# STM32.net
KiCad netlist of a schematic drawn in Altium Designer
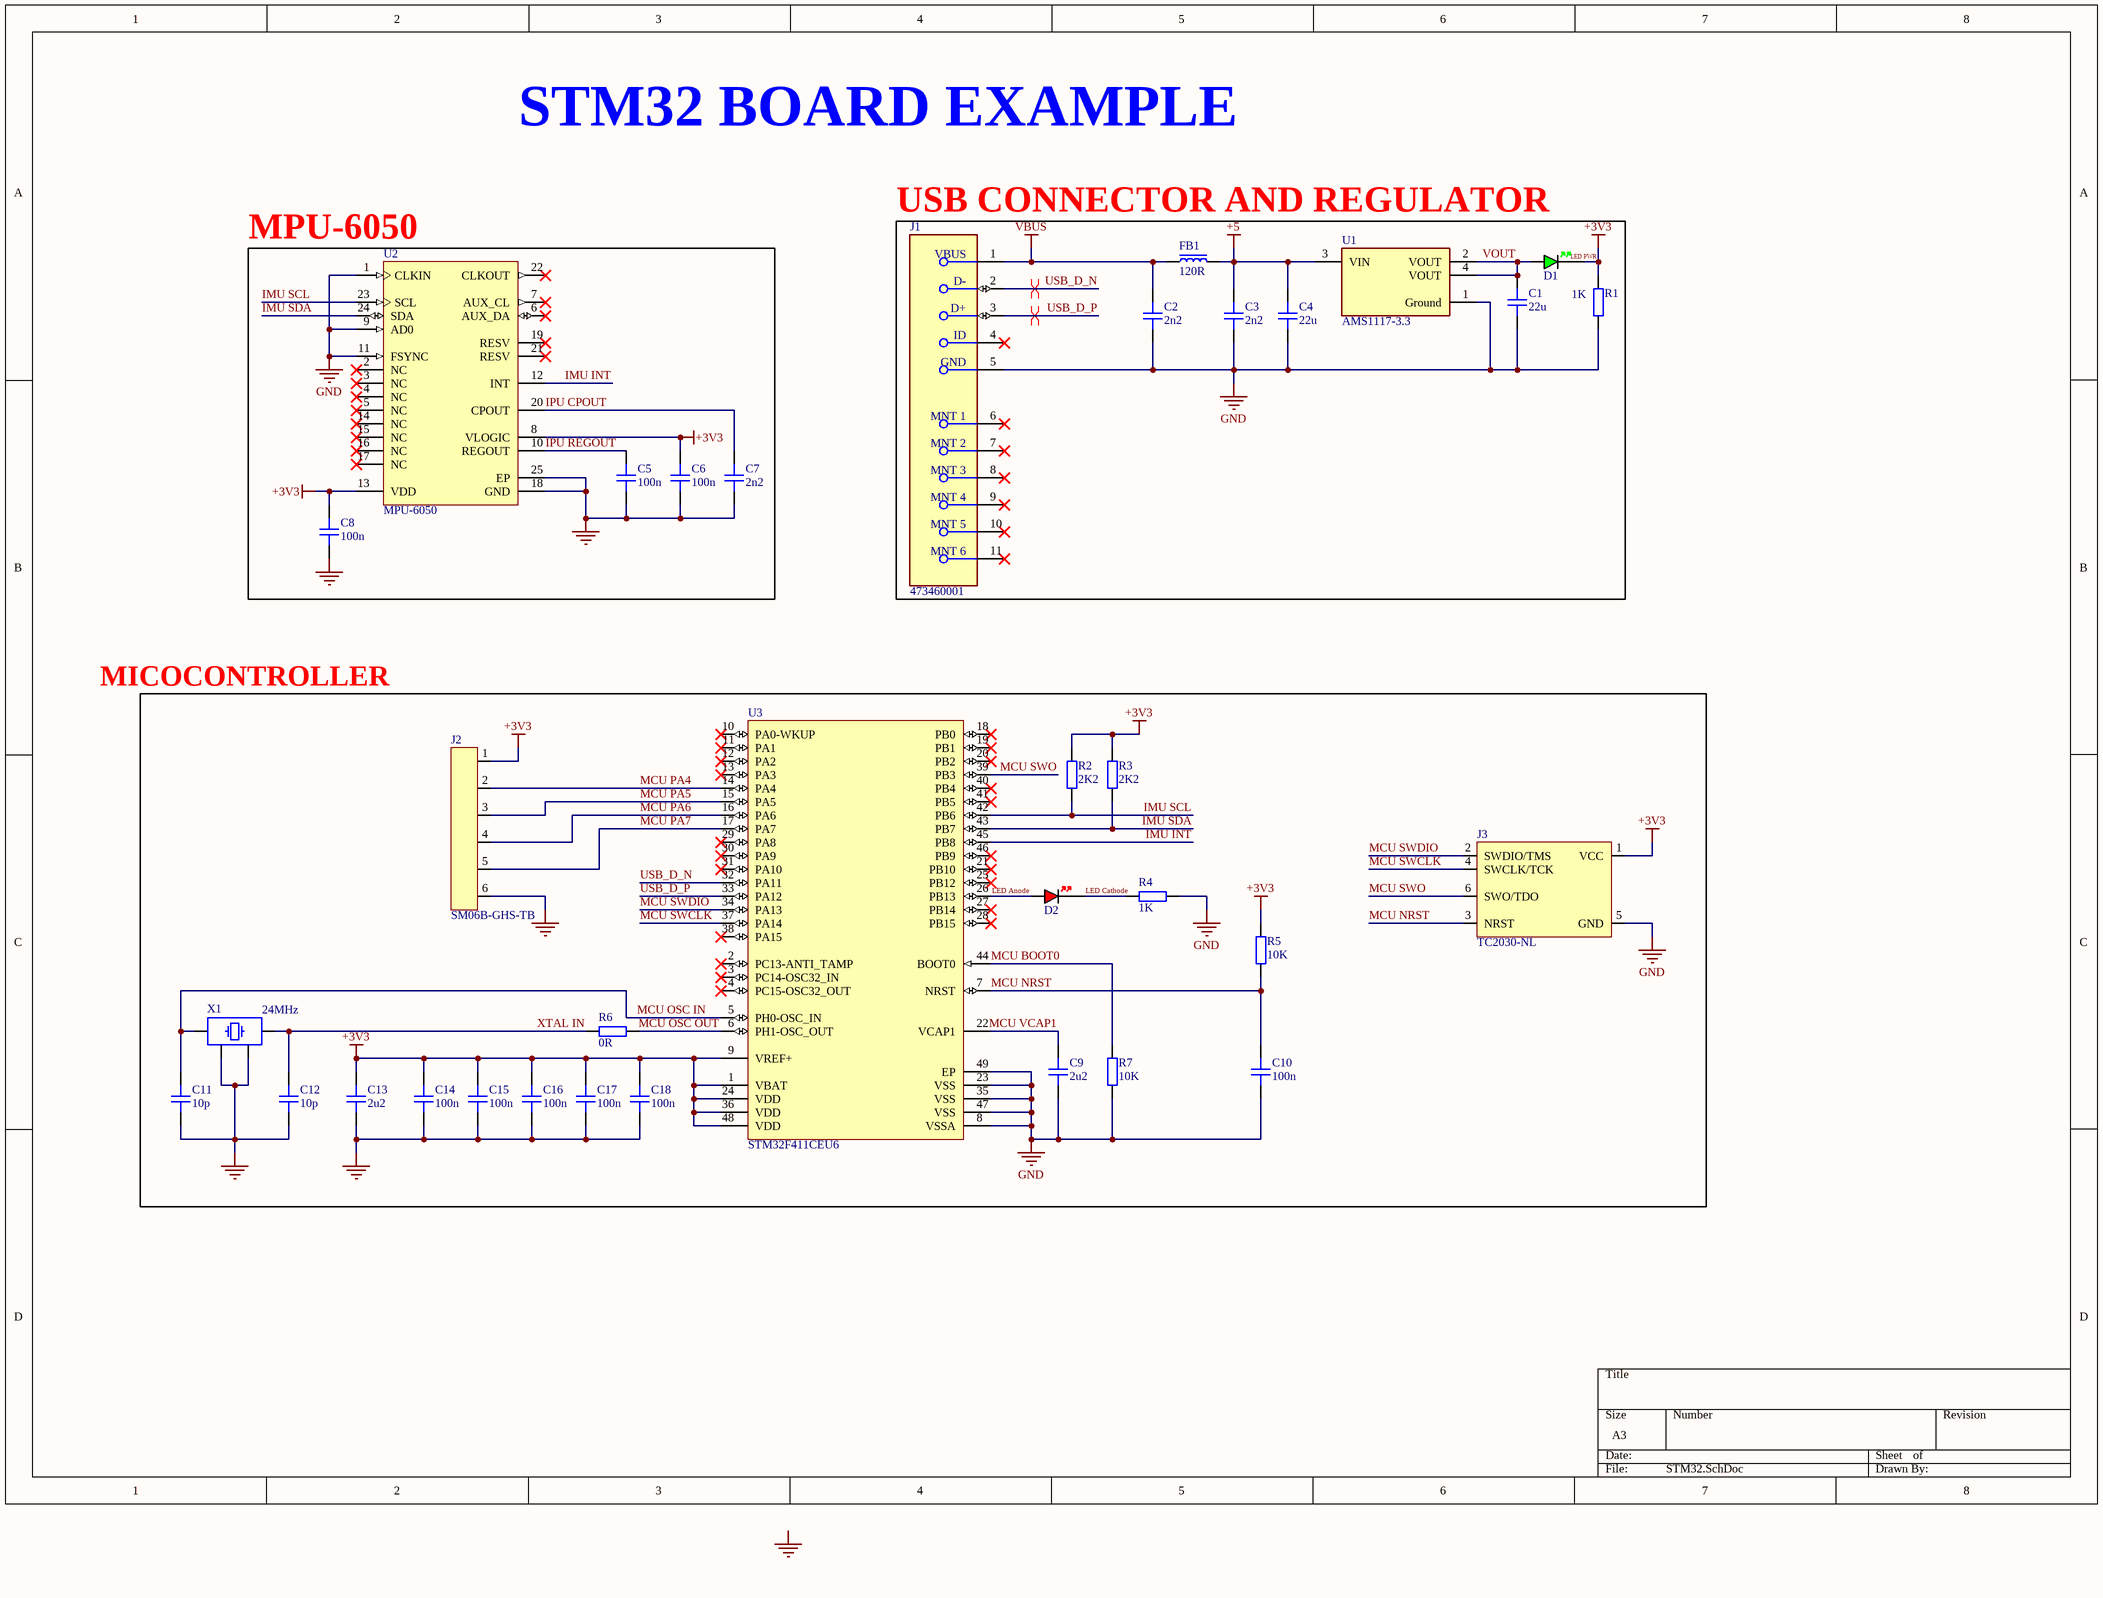
[diagram p0: STM32.SchDoc]

(export (version "E")
  (design (tool "Eeschema 10.0.6"))
  (components
    (comp (ref "C1")
      (value "22u")
      (footprint "CAP_0805")
      (description "Capacitor SMD 0805 16V")
      (libsource (lib "Schematic-Lib-PhilsLab") (part "CAP_0805_16V"))
    )
    (comp (ref "C2")
      (value "2n2")
      (footprint "CAP_0402")
      (description "Capacitor SMD 0402 16V")
      (libsource (lib "Schematic-Lib-PhilsLab") (part "CAP_0402_16V"))
    )
    (comp (ref "C3")
      (value "2n2")
      (footprint "CAP_0402")
      (description "Capacitor SMD 0402 16V")
      (libsource (lib "Schematic-Lib-PhilsLab") (part "CAP_0402_16V"))
    )
    (comp (ref "C4")
      (value "22u")
      (footprint "CAP_0805")
      (description "Capacitor SMD 0805 16V")
      (libsource (lib "Schematic-Lib-PhilsLab") (part "CAP_0805_16V"))
    )
    (comp (ref "C5")
      (value "100n")
      (footprint "CAP_0402")
      (description "Capacitor SMD 0402 16V")
      (libsource (lib "Schematic-Lib-PhilsLab") (part "CAP_0402_16V"))
    )
    (comp (ref "C6")
      (value "100n")
      (footprint "CAP_0402")
      (description "Capacitor SMD 0402 16V")
      (libsource (lib "Schematic-Lib-PhilsLab") (part "CAP_0402_16V"))
    )
    (comp (ref "C7")
      (value "2n2")
      (footprint "CAP_0402")
      (description "Capacitor SMD 0402 16V")
      (libsource (lib "Schematic-Lib-PhilsLab") (part "CAP_0402_16V"))
    )
    (comp (ref "C8")
      (value "100n")
      (footprint "CAP_0402")
      (description "Capacitor SMD 0402 16V")
      (libsource (lib "Schematic-Lib-PhilsLab") (part "CAP_0402_16V"))
    )
    (comp (ref "C9")
      (value "2u2")
      (footprint "CAP_0603")
      (description "Capacitor SMD 0603 16V")
      (libsource (lib "Schematic-Lib-PhilsLab") (part "CAP_0603_16V"))
    )
    (comp (ref "C10")
      (value "100n")
      (footprint "CAP_0402")
      (description "Capacitor SMD 0402 16V")
      (libsource (lib "Schematic-Lib-PhilsLab") (part "CAP_0402_16V"))
    )
    (comp (ref "C11")
      (value "10p")
      (footprint "CAP_0402")
      (description "Capacitor SMD 0402 16V")
      (libsource (lib "Schematic-Lib-PhilsLab") (part "CAP_0402_16V"))
    )
    (comp (ref "C12")
      (value "10p")
      (footprint "CAP_0402")
      (description "Capacitor SMD 0402 16V")
      (libsource (lib "Schematic-Lib-PhilsLab") (part "CAP_0402_16V"))
    )
    (comp (ref "C13")
      (value "2u2")
      (footprint "CAP_0603")
      (description "Capacitor SMD 0603 16V")
      (libsource (lib "Schematic-Lib-PhilsLab") (part "CAP_0603_16V"))
    )
    (comp (ref "C14")
      (value "100n")
      (footprint "CAP_0402")
      (description "Capacitor SMD 0402 16V")
      (libsource (lib "Schematic-Lib-PhilsLab") (part "CAP_0402_16V"))
    )
    (comp (ref "C15")
      (value "100n")
      (footprint "CAP_0402")
      (description "Capacitor SMD 0402 16V")
      (libsource (lib "Schematic-Lib-PhilsLab") (part "CAP_0402_16V"))
    )
    (comp (ref "C16")
      (value "100n")
      (footprint "CAP_0402")
      (description "Capacitor SMD 0402 16V")
      (libsource (lib "Schematic-Lib-PhilsLab") (part "CAP_0402_16V"))
    )
    (comp (ref "C17")
      (value "100n")
      (footprint "CAP_0402")
      (description "Capacitor SMD 0402 16V")
      (libsource (lib "Schematic-Lib-PhilsLab") (part "CAP_0402_16V"))
    )
    (comp (ref "C18")
      (value "100n")
      (footprint "CAP_0402")
      (description "Capacitor SMD 0402 16V")
      (libsource (lib "Schematic-Lib-PhilsLab") (part "CAP_0402_16V"))
    )
    (comp (ref "D1")
      (value "GREEN")
      (footprint "LED_0402_GREEN")
      (description "LED 0402 GREEN SMD")
      (libsource (lib "Schematic-Lib-PhilsLab") (part "LED_0402_GREEN"))
    )
    (comp (ref "D2")
      (value "RED")
      (footprint "LED_0402_RED")
      (description "LED 0402 RED SMD")
      (libsource (lib "Schematic-Lib-PhilsLab") (part "LED_0402_RED"))
    )
    (comp (ref "FB1")
      (value "120R")
      (footprint "FB_0603")
      (description "Ferrite Bead SMD 0603")
      (libsource (lib "Schematic-Lib-PhilsLab") (part "FB_0603"))
    )
    (comp (ref "J1")
      (value "473460001")
      (footprint "FP-473460001-MFG")
      (description "CONN RCPT USB2.0 MICRO B SMD R/A")
      (fields
        (field (name "OCTOPART") "https://octopart.com/47346-0001-molex-7164928")
        (field (name "MANUFACTURER") "Molex")
      )
      (libsource (lib "STMSch_Lib") (part "CMP-2000-05246-2"))
    )
    (comp (ref "J2")
      (value "SM06B-GHS-TB")
      (footprint "SM06B-GHS-TB")
      (description "Header Connector 6 Position 1.25MM Pitch SMD Horizontal JST GH")
      (fields (field (name "MANUFACTURER") "JST"))
      (libsource (lib "Schematic-Lib-PhilsLab") (part "SM06B-GHS-TB"))
    )
    (comp (ref "J3")
      (value "TC2030-NL")
      (footprint "TC2030-NL-FP")
      (description "Tag-Connect No-Solder SWD Debug Connector (No Legs) DO NOT PLACE")
      (fields
        (field (name "MANUFACTURER") "Tag-Connect")
        (field (name "MANUFACTURER PART NUMBER") "TC2030-NL-FP")
      )
      (libsource (lib "Schematic-Lib-PhilsLab") (part "TC2030-NL"))
    )
    (comp (ref "R1")
      (value "1K")
      (footprint "RES_0402")
      (description "Resistor SMD 0402")
      (libsource (lib "Schematic-Lib-PhilsLab") (part "RES_0402"))
    )
    (comp (ref "R2")
      (value "2K2")
      (footprint "RES_0402")
      (description "Resistor SMD 0402")
      (libsource (lib "Schematic-Lib-PhilsLab") (part "RES_0402"))
    )
    (comp (ref "R3")
      (value "2K2")
      (footprint "RES_0402")
      (description "Resistor SMD 0402")
      (libsource (lib "Schematic-Lib-PhilsLab") (part "RES_0402"))
    )
    (comp (ref "R4")
      (value "1K")
      (footprint "RES_0402")
      (description "Resistor SMD 0402")
      (libsource (lib "Schematic-Lib-PhilsLab") (part "RES_0402"))
    )
    (comp (ref "R5")
      (value "10K")
      (footprint "RES_0402")
      (description "Resistor SMD 0402")
      (libsource (lib "Schematic-Lib-PhilsLab") (part "RES_0402"))
    )
    (comp (ref "R6")
      (value "0R")
      (footprint "RES_0402")
      (description "Resistor SMD 0402")
      (libsource (lib "Schematic-Lib-PhilsLab") (part "RES_0402"))
    )
    (comp (ref "R7")
      (value "10K")
      (footprint "RES_0402")
      (description "Resistor SMD 0402")
      (libsource (lib "Schematic-Lib-PhilsLab") (part "RES_0402"))
    )
    (comp (ref "U1")
      (value "AMS1117-3.3")
      (footprint "FP-AMS1117-IPC_A")
      (description "LDO Voltage Regulators 1A, 3.3V")
      (fields
        (field (name "OCTOPART") "https://octopart.com/ams1117-3.3-advanced+monolithic+systems-25899300")
        (field (name "MANUFACTURER") "Advanced Monolithic Systems")
      )
      (libsource (lib "STMSch_Lib") (part "CMP-209535-000001-1"))
    )
    (comp (ref "U2")
      (value "MPU-6050")
      (footprint "IS-QFN-24_V")
      (fields (field (name "MANUFACTURER") "InvenSense"))
      (libsource (lib "STMSch_Lib") (part "CMP-1753-00002-2"))
    )
    (comp (ref "U3")
      (value "STM32F411CEU6")
      (footprint "STM-UFQFPN48_L")
      (libsource (lib "STMSch_Lib") (part "CMP-0243-00165-1"))
    )
    (comp (ref "X1")
      (value "24MHz")
      (footprint "XTAL_3225")
      (description "Crystal SMD 24MHz 10PPM 7pF 3225")
      (fields
        (field (name "MANUFACTURER") "Epson")
        (field (name "MANUFACTURER PART NUMBER") "TSX-3225 24.0000MF15X-AC")
      )
      (libsource (lib "Schematic-Lib-PhilsLab") (part "TSX-3225_24.0000MF15X-AC"))
    )
  )
  (nets
    (net (code "1") (name "+3V3") (class "Default")
      (node (ref "C13") (pin "2") (pinfunction "2_2") (pintype "passive"))
      (node (ref "C14") (pin "2") (pinfunction "2_2") (pintype "passive"))
      (node (ref "C15") (pin "2") (pinfunction "2_2") (pintype "passive"))
      (node (ref "C16") (pin "2") (pinfunction "2_2") (pintype "passive"))
      (node (ref "C17") (pin "2") (pinfunction "2_2") (pintype "passive"))
      (node (ref "C18") (pin "2") (pinfunction "2_2") (pintype "passive"))
      (node (ref "C6") (pin "2") (pinfunction "2_2") (pintype "passive"))
      (node (ref "C8") (pin "2") (pinfunction "2_2") (pintype "passive"))
      (node (ref "D1") (pin "K") (pinfunction "K_K") (pintype "passive"))
      (node (ref "J2") (pin "1") (pinfunction "1_1") (pintype "passive"))
      (node (ref "J3") (pin "1") (pinfunction "VCC_1") (pintype "passive"))
      (node (ref "R1") (pin "2") (pinfunction "2_2") (pintype "passive"))
      (node (ref "R2") (pin "2") (pinfunction "2_2") (pintype "passive"))
      (node (ref "R3") (pin "2") (pinfunction "2_2") (pintype "passive"))
      (node (ref "R5") (pin "2") (pinfunction "2_2") (pintype "passive"))
      (node (ref "U2") (pin "13") (pinfunction "VDD_13") (pintype "power_in"))
      (node (ref "U2") (pin "8") (pinfunction "VLOGIC_8") (pintype "power_in"))
      (node (ref "U3") (pin "1") (pinfunction "VBAT_1") (pintype "power_in"))
      (node (ref "U3") (pin "24") (pinfunction "VDD_24") (pintype "power_in"))
      (node (ref "U3") (pin "36") (pinfunction "VDD_36") (pintype "power_in"))
      (node (ref "U3") (pin "48") (pinfunction "VDD_48") (pintype "power_in"))
      (node (ref "U3") (pin "9") (pinfunction "VREF+_9") (pintype "power_in"))
    )
    (net (code "2") (name "+5") (class "Default")
      (node (ref "C3") (pin "2") (pinfunction "2_2") (pintype "passive"))
      (node (ref "C4") (pin "2") (pinfunction "2_2") (pintype "passive"))
      (node (ref "FB1") (pin "2") (pinfunction "2_2") (pintype "passive"))
      (node (ref "U1") (pin "3") (pinfunction "VIN_3") (pintype "power_in"))
    )
    (net (code "3") (name "/IMU INT") (class "Default")
      (node (ref "U2") (pin "12") (pinfunction "INT_12") (pintype "open_collector"))
      (node (ref "U3") (pin "45") (pinfunction "PB8_45") (pintype "bidirectional"))
    )
    (net (code "4") (name "/IMU SCL") (class "Default")
      (node (ref "R2") (pin "1") (pinfunction "1_1") (pintype "passive"))
      (node (ref "U2") (pin "23") (pinfunction "SCL_23") (pintype "input"))
      (node (ref "U3") (pin "42") (pinfunction "PB6_42") (pintype "bidirectional"))
    )
    (net (code "5") (name "/IMU SDA") (class "Default")
      (node (ref "R3") (pin "1") (pinfunction "1_1") (pintype "passive"))
      (node (ref "U2") (pin "24") (pinfunction "SDA_24") (pintype "bidirectional"))
      (node (ref "U3") (pin "43") (pinfunction "PB7_43") (pintype "bidirectional"))
    )
    (net (code "6") (name "/IPU CPOUT") (class "Default")
      (node (ref "C7") (pin "2") (pinfunction "2_2") (pintype "passive"))
      (node (ref "U2") (pin "20") (pinfunction "CPOUT_20") (pintype "passive"))
    )
    (net (code "7") (name "/IPU REGOUT") (class "Default")
      (node (ref "C5") (pin "2") (pinfunction "2_2") (pintype "passive"))
      (node (ref "U2") (pin "10") (pinfunction "REGOUT_10") (pintype "passive"))
    )
    (net (code "8") (name "/LED Anode") (class "Default")
      (node (ref "D2") (pin "A") (pinfunction "A_A") (pintype "passive"))
      (node (ref "U3") (pin "26") (pinfunction "PB13_26") (pintype "bidirectional"))
    )
    (net (code "9") (name "/LED Cathode") (class "Default")
      (node (ref "D2") (pin "K") (pinfunction "K_K") (pintype "passive"))
      (node (ref "R4") (pin "2") (pinfunction "2_2") (pintype "passive"))
    )
    (net (code "10") (name "/MCU BOOT0") (class "Default")
      (node (ref "R7") (pin "2") (pinfunction "2_2") (pintype "passive"))
      (node (ref "U3") (pin "44") (pinfunction "BOOT0_44") (pintype "input"))
    )
    (net (code "11") (name "/MCU NRST") (class "Default")
      (node (ref "C10") (pin "2") (pinfunction "2_2") (pintype "passive"))
      (node (ref "J3") (pin "3") (pinfunction "NRST_3") (pintype "passive"))
      (node (ref "R5") (pin "1") (pinfunction "1_1") (pintype "passive"))
      (node (ref "U3") (pin "7") (pinfunction "NRST_7") (pintype "bidirectional"))
    )
    (net (code "12") (name "/MCU OSC IN") (class "Default")
      (node (ref "C11") (pin "2") (pinfunction "2_2") (pintype "passive"))
      (node (ref "U3") (pin "5") (pinfunction "PH0-OSC_IN_5") (pintype "bidirectional"))
      (node (ref "X1") (pin "1") (pinfunction "1_1") (pintype "passive"))
    )
    (net (code "13") (name "/MCU OSC OUT") (class "Default")
      (node (ref "R6") (pin "2") (pinfunction "2_2") (pintype "passive"))
      (node (ref "U3") (pin "6") (pinfunction "PH1-OSC_OUT_6") (pintype "bidirectional"))
    )
    (net (code "14") (name "/MCU PA4") (class "Default")
      (node (ref "J2") (pin "2") (pinfunction "2_2") (pintype "passive"))
      (node (ref "U3") (pin "14") (pinfunction "PA4_14") (pintype "bidirectional"))
    )
    (net (code "15") (name "/MCU PA5") (class "Default")
      (node (ref "J2") (pin "3") (pinfunction "3_3") (pintype "passive"))
      (node (ref "U3") (pin "15") (pinfunction "PA5_15") (pintype "bidirectional"))
    )
    (net (code "16") (name "/MCU PA6") (class "Default")
      (node (ref "J2") (pin "4") (pinfunction "4_4") (pintype "passive"))
      (node (ref "U3") (pin "16") (pinfunction "PA6_16") (pintype "bidirectional"))
    )
    (net (code "17") (name "/MCU PA7") (class "Default")
      (node (ref "J2") (pin "5") (pinfunction "5_5") (pintype "passive"))
      (node (ref "U3") (pin "17") (pinfunction "PA7_17") (pintype "bidirectional"))
    )
    (net (code "18") (name "/MCU SWCLK") (class "Default")
      (node (ref "J3") (pin "4") (pinfunction "SWCLK/TCK_4") (pintype "passive"))
      (node (ref "U3") (pin "37") (pinfunction "PA14_37") (pintype "bidirectional"))
    )
    (net (code "19") (name "/MCU SWDIO") (class "Default")
      (node (ref "J3") (pin "2") (pinfunction "SWDIO/TMS_2") (pintype "passive"))
      (node (ref "U3") (pin "34") (pinfunction "PA13_34") (pintype "bidirectional"))
    )
    (net (code "20") (name "/MCU SWO") (class "Default")
      (node (ref "J3") (pin "6") (pinfunction "SWO/TDO_6") (pintype "passive"))
      (node (ref "U3") (pin "39") (pinfunction "PB3_39") (pintype "bidirectional"))
    )
    (net (code "21") (name "/MCU VCAP1") (class "Default")
      (node (ref "C9") (pin "2") (pinfunction "2_2") (pintype "passive"))
      (node (ref "U3") (pin "22") (pinfunction "VCAP1_22") (pintype "passive"))
    )
    (net (code "22") (name "/USB_D_N") (class "Default")
      (node (ref "J1") (pin "2") (pinfunction "D-_2") (pintype "bidirectional"))
      (node (ref "U3") (pin "32") (pinfunction "PA11_32") (pintype "bidirectional"))
    )
    (net (code "23") (name "/USB_D_P") (class "Default")
      (node (ref "J1") (pin "3") (pinfunction "D+_3") (pintype "bidirectional"))
      (node (ref "U3") (pin "33") (pinfunction "PA12_33") (pintype "bidirectional"))
    )
    (net (code "24") (name "/VOUT") (class "Default")
      (node (ref "C1") (pin "2") (pinfunction "2_2") (pintype "passive"))
      (node (ref "D1") (pin "A") (pinfunction "A_A") (pintype "passive"))
      (node (ref "U1") (pin "2") (pinfunction "VOUT_2") (pintype "passive"))
      (node (ref "U1") (pin "4") (pinfunction "VOUT_4") (pintype "passive"))
    )
    (net (code "25") (name "/XTAL IN") (class "Default")
      (node (ref "C12") (pin "2") (pinfunction "2_2") (pintype "passive"))
      (node (ref "R6") (pin "1") (pinfunction "1_1") (pintype "passive"))
      (node (ref "X1") (pin "3") (pinfunction "3_3") (pintype "passive"))
    )
    (net (code "26") (name "GND") (class "Default")
      (node (ref "C1") (pin "1") (pinfunction "1_1") (pintype "passive"))
      (node (ref "C10") (pin "1") (pinfunction "1_1") (pintype "passive"))
      (node (ref "C11") (pin "1") (pinfunction "1_1") (pintype "passive"))
      (node (ref "C12") (pin "1") (pinfunction "1_1") (pintype "passive"))
      (node (ref "C13") (pin "1") (pinfunction "1_1") (pintype "passive"))
      (node (ref "C14") (pin "1") (pinfunction "1_1") (pintype "passive"))
      (node (ref "C15") (pin "1") (pinfunction "1_1") (pintype "passive"))
      (node (ref "C16") (pin "1") (pinfunction "1_1") (pintype "passive"))
      (node (ref "C17") (pin "1") (pinfunction "1_1") (pintype "passive"))
      (node (ref "C18") (pin "1") (pinfunction "1_1") (pintype "passive"))
      (node (ref "C2") (pin "1") (pinfunction "1_1") (pintype "passive"))
      (node (ref "C3") (pin "1") (pinfunction "1_1") (pintype "passive"))
      (node (ref "C4") (pin "1") (pinfunction "1_1") (pintype "passive"))
      (node (ref "C5") (pin "1") (pinfunction "1_1") (pintype "passive"))
      (node (ref "C6") (pin "1") (pinfunction "1_1") (pintype "passive"))
      (node (ref "C7") (pin "1") (pinfunction "1_1") (pintype "passive"))
      (node (ref "C8") (pin "1") (pinfunction "1_1") (pintype "passive"))
      (node (ref "C9") (pin "1") (pinfunction "1_1") (pintype "passive"))
      (node (ref "J1") (pin "5") (pinfunction "GND_5") (pintype "power_in"))
      (node (ref "J2") (pin "6") (pinfunction "6_6") (pintype "passive"))
      (node (ref "J3") (pin "5") (pinfunction "GND_5") (pintype "passive"))
      (node (ref "R1") (pin "1") (pinfunction "1_1") (pintype "passive"))
      (node (ref "R4") (pin "1") (pinfunction "1_1") (pintype "passive"))
      (node (ref "R7") (pin "1") (pinfunction "1_1") (pintype "passive"))
      (node (ref "U1") (pin "1") (pinfunction "Ground_1") (pintype "power_in"))
      (node (ref "U2") (pin "1") (pinfunction "CLKIN_1") (pintype "input"))
      (node (ref "U2") (pin "11") (pinfunction "FSYNC_11") (pintype "input"))
      (node (ref "U2") (pin "18") (pinfunction "GND_18") (pintype "power_in"))
      (node (ref "U2") (pin "25") (pinfunction "EP_25") (pintype "power_in"))
      (node (ref "U2") (pin "9") (pinfunction "AD0_9") (pintype "input"))
      (node (ref "U3") (pin "23") (pinfunction "VSS_23") (pintype "power_in"))
      (node (ref "U3") (pin "35") (pinfunction "VSS_35") (pintype "power_in"))
      (node (ref "U3") (pin "47") (pinfunction "VSS_47") (pintype "power_in"))
      (node (ref "U3") (pin "49") (pinfunction "EP_49") (pintype "power_in"))
      (node (ref "U3") (pin "8") (pinfunction "VSSA_8") (pintype "power_in"))
      (node (ref "X1") (pin "2") (pinfunction "2_2") (pintype "passive"))
      (node (ref "X1") (pin "4") (pinfunction "4_4") (pintype "passive"))
    )
    (net (code "27") (name "VBUS") (class "Default")
      (node (ref "C2") (pin "2") (pinfunction "2_2") (pintype "passive"))
      (node (ref "FB1") (pin "1") (pinfunction "1_1") (pintype "passive"))
      (node (ref "J1") (pin "1") (pinfunction "VBUS_1") (pintype "power_in"))
    )
    (net (code "28") (name "unconnected-(J1-ID-Pad4)") (class "Default")
      (node (ref "J1") (pin "4") (pinfunction "ID_4") (pintype "passive+no_connect"))
    )
    (net (code "29") (name "unconnected-(J1-MNT_1-Pad6)") (class "Default")
      (node (ref "J1") (pin "6") (pinfunction "MNT_1_6") (pintype "passive+no_connect"))
    )
    (net (code "30") (name "unconnected-(J1-MNT_2-Pad7)") (class "Default")
      (node (ref "J1") (pin "7") (pinfunction "MNT_2_7") (pintype "passive+no_connect"))
    )
    (net (code "31") (name "unconnected-(J1-MNT_3-Pad8)") (class "Default")
      (node (ref "J1") (pin "8") (pinfunction "MNT_3_8") (pintype "passive+no_connect"))
    )
    (net (code "32") (name "unconnected-(J1-MNT_4-Pad9)") (class "Default")
      (node (ref "J1") (pin "9") (pinfunction "MNT_4_9") (pintype "passive+no_connect"))
    )
    (net (code "33") (name "unconnected-(J1-MNT_5-Pad10)") (class "Default")
      (node (ref "J1") (pin "10") (pinfunction "MNT_5_10") (pintype "passive+no_connect"))
    )
    (net (code "34") (name "unconnected-(J1-MNT_6-Pad11)") (class "Default")
      (node (ref "J1") (pin "11") (pinfunction "MNT_6_11") (pintype "passive+no_connect"))
    )
    (net (code "35") (name "unconnected-(U2-AUX_CL-Pad7)") (class "Default")
      (node (ref "U2") (pin "7") (pinfunction "AUX_CL_7") (pintype "output+no_connect"))
    )
    (net (code "36") (name "unconnected-(U2-AUX_DA-Pad6)") (class "Default")
      (node (ref "U2") (pin "6") (pinfunction "AUX_DA_6") (pintype "bidirectional+no_connect"))
    )
    (net (code "37") (name "unconnected-(U2-CLKOUT-Pad22)") (class "Default")
      (node (ref "U2") (pin "22") (pinfunction "CLKOUT_22") (pintype "output+no_connect"))
    )
    (net (code "38") (name "unconnected-(U2-NC-Pad2)") (class "Default")
      (node (ref "U2") (pin "2") (pinfunction "NC_2") (pintype "passive+no_connect"))
    )
    (net (code "39") (name "unconnected-(U2-NC-Pad3)") (class "Default")
      (node (ref "U2") (pin "3") (pinfunction "NC_3") (pintype "passive+no_connect"))
    )
    (net (code "40") (name "unconnected-(U2-NC-Pad4)") (class "Default")
      (node (ref "U2") (pin "4") (pinfunction "NC_4") (pintype "passive+no_connect"))
    )
    (net (code "41") (name "unconnected-(U2-NC-Pad5)") (class "Default")
      (node (ref "U2") (pin "5") (pinfunction "NC_5") (pintype "passive+no_connect"))
    )
    (net (code "42") (name "unconnected-(U2-NC-Pad14)") (class "Default")
      (node (ref "U2") (pin "14") (pinfunction "NC_14") (pintype "passive+no_connect"))
    )
    (net (code "43") (name "unconnected-(U2-NC-Pad15)") (class "Default")
      (node (ref "U2") (pin "15") (pinfunction "NC_15") (pintype "passive+no_connect"))
    )
    (net (code "44") (name "unconnected-(U2-NC-Pad16)") (class "Default")
      (node (ref "U2") (pin "16") (pinfunction "NC_16") (pintype "passive+no_connect"))
    )
    (net (code "45") (name "unconnected-(U2-NC-Pad17)") (class "Default")
      (node (ref "U2") (pin "17") (pinfunction "NC_17") (pintype "passive+no_connect"))
    )
    (net (code "46") (name "unconnected-(U2-RESV-Pad19)") (class "Default")
      (node (ref "U2") (pin "19") (pinfunction "RESV_19") (pintype "passive+no_connect"))
    )
    (net (code "47") (name "unconnected-(U2-RESV-Pad21)") (class "Default")
      (node (ref "U2") (pin "21") (pinfunction "RESV_21") (pintype "passive+no_connect"))
    )
    (net (code "48") (name "unconnected-(U3-PA0-WKUP-Pad10)") (class "Default")
      (node (ref "U3") (pin "10") (pinfunction "PA0-WKUP_10") (pintype "bidirectional+no_connect"))
    )
    (net (code "49") (name "unconnected-(U3-PA1-Pad11)") (class "Default")
      (node (ref "U3") (pin "11") (pinfunction "PA1_11") (pintype "bidirectional+no_connect"))
    )
    (net (code "50") (name "unconnected-(U3-PA2-Pad12)") (class "Default")
      (node (ref "U3") (pin "12") (pinfunction "PA2_12") (pintype "bidirectional+no_connect"))
    )
    (net (code "51") (name "unconnected-(U3-PA3-Pad13)") (class "Default")
      (node (ref "U3") (pin "13") (pinfunction "PA3_13") (pintype "bidirectional+no_connect"))
    )
    (net (code "52") (name "unconnected-(U3-PA8-Pad29)") (class "Default")
      (node (ref "U3") (pin "29") (pinfunction "PA8_29") (pintype "bidirectional+no_connect"))
    )
    (net (code "53") (name "unconnected-(U3-PA9-Pad30)") (class "Default")
      (node (ref "U3") (pin "30") (pinfunction "PA9_30") (pintype "bidirectional+no_connect"))
    )
    (net (code "54") (name "unconnected-(U3-PA10-Pad31)") (class "Default")
      (node (ref "U3") (pin "31") (pinfunction "PA10_31") (pintype "bidirectional+no_connect"))
    )
    (net (code "55") (name "unconnected-(U3-PA15-Pad38)") (class "Default")
      (node (ref "U3") (pin "38") (pinfunction "PA15_38") (pintype "bidirectional+no_connect"))
    )
    (net (code "56") (name "unconnected-(U3-PB0-Pad18)") (class "Default")
      (node (ref "U3") (pin "18") (pinfunction "PB0_18") (pintype "bidirectional+no_connect"))
    )
    (net (code "57") (name "unconnected-(U3-PB1-Pad19)") (class "Default")
      (node (ref "U3") (pin "19") (pinfunction "PB1_19") (pintype "bidirectional+no_connect"))
    )
    (net (code "58") (name "unconnected-(U3-PB2-Pad20)") (class "Default")
      (node (ref "U3") (pin "20") (pinfunction "PB2_20") (pintype "bidirectional+no_connect"))
    )
    (net (code "59") (name "unconnected-(U3-PB4-Pad40)") (class "Default")
      (node (ref "U3") (pin "40") (pinfunction "PB4_40") (pintype "bidirectional+no_connect"))
    )
    (net (code "60") (name "unconnected-(U3-PB5-Pad41)") (class "Default")
      (node (ref "U3") (pin "41") (pinfunction "PB5_41") (pintype "bidirectional+no_connect"))
    )
    (net (code "61") (name "unconnected-(U3-PB9-Pad46)") (class "Default")
      (node (ref "U3") (pin "46") (pinfunction "PB9_46") (pintype "bidirectional+no_connect"))
    )
    (net (code "62") (name "unconnected-(U3-PB10-Pad21)") (class "Default")
      (node (ref "U3") (pin "21") (pinfunction "PB10_21") (pintype "bidirectional+no_connect"))
    )
    (net (code "63") (name "unconnected-(U3-PB12-Pad25)") (class "Default")
      (node (ref "U3") (pin "25") (pinfunction "PB12_25") (pintype "bidirectional+no_connect"))
    )
    (net (code "64") (name "unconnected-(U3-PB14-Pad27)") (class "Default")
      (node (ref "U3") (pin "27") (pinfunction "PB14_27") (pintype "bidirectional+no_connect"))
    )
    (net (code "65") (name "unconnected-(U3-PB15-Pad28)") (class "Default")
      (node (ref "U3") (pin "28") (pinfunction "PB15_28") (pintype "bidirectional+no_connect"))
    )
    (net (code "66") (name "unconnected-(U3-PC13-ANTI_TAMP-Pad2)") (class "Default")
      (node (ref "U3") (pin "2") (pinfunction "PC13-ANTI_TAMP_2") (pintype "bidirectional+no_connect"))
    )
    (net (code "67") (name "unconnected-(U3-PC14-OSC32_IN-Pad3)") (class "Default")
      (node (ref "U3") (pin "3") (pinfunction "PC14-OSC32_IN_3") (pintype "bidirectional+no_connect"))
    )
    (net (code "68") (name "unconnected-(U3-PC15-OSC32_OUT-Pad4)") (class "Default")
      (node (ref "U3") (pin "4") (pinfunction "PC15-OSC32_OUT_4") (pintype "bidirectional+no_connect"))
    )
  )
)
